# HeadAmp.net
KiCad netlist of a schematic drawn in EAGLE
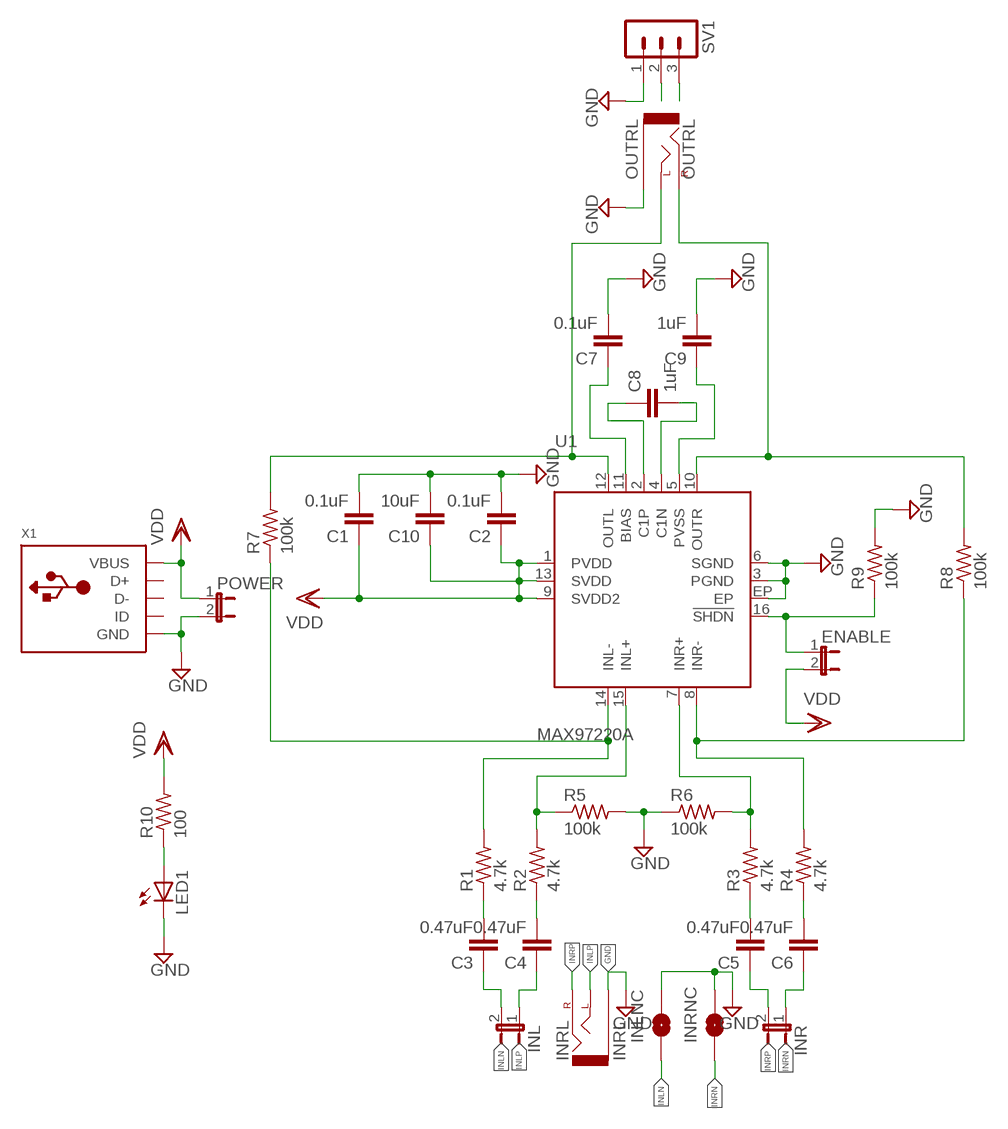
[diagram p0: schematic, sheet 1]

(export (version "E")
  (design (tool "Eeschema 10.0.6"))
  (components
    (comp (ref "C1")
      (value "0.1uF")
      (footprint "eagle-import:C0603")
      (libsource (lib "eagle-import") (part "C-EUC0603"))
    )
    (comp (ref "C2")
      (value "0.1uF")
      (footprint "eagle-import:C0603")
      (libsource (lib "eagle-import") (part "C-EUC0603"))
    )
    (comp (ref "C3")
      (value "0.47uF")
      (footprint "eagle-import:C0603")
      (libsource (lib "eagle-import") (part "C-EUC0603"))
    )
    (comp (ref "C4")
      (value "0.47uF")
      (footprint "eagle-import:C0603")
      (libsource (lib "eagle-import") (part "C-EUC0603"))
    )
    (comp (ref "C5")
      (value "0.47uF")
      (footprint "eagle-import:C0603")
      (libsource (lib "eagle-import") (part "C-EUC0603"))
    )
    (comp (ref "C6")
      (value "0.47uF")
      (footprint "eagle-import:C0603")
      (libsource (lib "eagle-import") (part "C-EUC0603"))
    )
    (comp (ref "C7")
      (value "0.1uF")
      (footprint "eagle-import:C0603")
      (libsource (lib "eagle-import") (part "C-EUC0603"))
    )
    (comp (ref "C8")
      (value "1uF")
      (footprint "eagle-import:C0603")
      (libsource (lib "eagle-import") (part "C-EUC0603"))
    )
    (comp (ref "C9")
      (value "1uF")
      (footprint "eagle-import:C0603")
      (libsource (lib "eagle-import") (part "C-EUC0603"))
    )
    (comp (ref "C10")
      (value "10uF")
      (footprint "eagle-import:C0603")
      (libsource (lib "eagle-import") (part "C-EUC0603"))
    )
    (comp (ref "ENABLE")
      (value "JP1E")
      (footprint "eagle-import:JP1")
      (libsource (lib "eagle-import") (part "JP1E"))
    )
    (comp (ref "INL")
      (value "JP1E")
      (footprint "eagle-import:JP1")
      (libsource (lib "eagle-import") (part "JP1E"))
    )
    (comp (ref "INLNC")
      (value "SOLDERJUMPERNO")
      (footprint "eagle-import:SJ_2S-NO")
      (libsource (lib "eagle-import") (part "SOLDERJUMPERNO"))
    )
    (comp (ref "INR")
      (value "JP1E")
      (footprint "eagle-import:JP1")
      (libsource (lib "eagle-import") (part "JP1E"))
    )
    (comp (ref "INRL")
      (value "INRL")
      (footprint "eagle-import:AUDIO-JACK-3.5MM-SMD")
      (libsource (lib "eagle-import") (part "AUDIO-JACKSMD2"))
    )
    (comp (ref "INRNC")
      (value "SOLDERJUMPERNO")
      (footprint "eagle-import:SJ_2S-NO")
      (libsource (lib "eagle-import") (part "SOLDERJUMPERNO"))
    )
    (comp (ref "LED1")
      (value "LEDCHIP-LED0805")
      (footprint "eagle-import:CHIP-LED0805")
      (libsource (lib "eagle-import") (part "LEDCHIP-LED0805"))
    )
    (comp (ref "OUTRL")
      (value "OUTRL")
      (footprint "eagle-import:AUDIO-JACK-3.5MM-SMD")
      (libsource (lib "eagle-import") (part "AUDIO-JACKSMD2"))
    )
    (comp (ref "POWER")
      (value "JP1E")
      (footprint "eagle-import:JP1")
      (libsource (lib "eagle-import") (part "JP1E"))
    )
    (comp (ref "R1")
      (value "4.7k")
      (footprint "eagle-import:R0603")
      (libsource (lib "eagle-import") (part "R-US_R0603"))
    )
    (comp (ref "R2")
      (value "4.7k")
      (footprint "eagle-import:R0603")
      (libsource (lib "eagle-import") (part "R-US_R0603"))
    )
    (comp (ref "R3")
      (value "4.7k")
      (footprint "eagle-import:R0603")
      (libsource (lib "eagle-import") (part "R-US_R0603"))
    )
    (comp (ref "R4")
      (value "4.7k")
      (footprint "eagle-import:R0603")
      (libsource (lib "eagle-import") (part "R-US_R0603"))
    )
    (comp (ref "R5")
      (value "100k")
      (footprint "eagle-import:R0603")
      (libsource (lib "eagle-import") (part "R-US_R0603"))
    )
    (comp (ref "R6")
      (value "100k")
      (footprint "eagle-import:R0603")
      (libsource (lib "eagle-import") (part "R-US_R0603"))
    )
    (comp (ref "R7")
      (value "100k")
      (footprint "eagle-import:R0603")
      (libsource (lib "eagle-import") (part "R-US_R0603"))
    )
    (comp (ref "R8")
      (value "100k")
      (footprint "eagle-import:R0603")
      (libsource (lib "eagle-import") (part "R-US_R0603"))
    )
    (comp (ref "R9")
      (value "100k")
      (footprint "eagle-import:R0603")
      (libsource (lib "eagle-import") (part "R-US_R0603"))
    )
    (comp (ref "R10")
      (value "100")
      (footprint "eagle-import:R0603")
      (libsource (lib "eagle-import") (part "R-US_R0603"))
    )
    (comp (ref "SV1")
      (value "MA03-1")
      (footprint "eagle-import:MA03-1")
      (libsource (lib "eagle-import") (part "MA03-1"))
    )
    (comp (ref "U1")
      (value "MAX97220A")
      (footprint "eagle-import:TQFN16")
      (libsource (lib "eagle-import") (part "MAX97220A"))
    )
    (comp (ref "X1")
      (value "USB_MICRO_20329_V2")
      (footprint "eagle-import:4UCONN_20329_V2")
      (libsource (lib "eagle-import") (part "USB_MICRO_20329_V2"))
    )
  )
  (nets
    (net (code "1") (name "/LOUT") (class "Default")
      (node (ref "OUTRL") (pin "4") (pinfunction "4_4") (pintype "bidirectional"))
      (node (ref "R7") (pin "2") (pinfunction "2_2") (pintype "passive"))
      (node (ref "SV1") (pin "2") (pinfunction "2_2") (pintype "passive"))
      (node (ref "U1") (pin "12") (pinfunction "OUTL_12") (pintype "output"))
    )
    (net (code "2") (name "/ROUT") (class "Default")
      (node (ref "OUTRL") (pin "1") (pinfunction "1_1") (pintype "bidirectional"))
      (node (ref "R8") (pin "2") (pinfunction "2_2") (pintype "passive"))
      (node (ref "SV1") (pin "3") (pinfunction "3_3") (pintype "passive"))
      (node (ref "U1") (pin "10") (pinfunction "OUTR_10") (pintype "output"))
    )
    (net (code "3") (name "GND") (class "Default")
      (node (ref "C1") (pin "2") (pinfunction "2_2") (pintype "passive"))
      (node (ref "C10") (pin "2") (pinfunction "2_2") (pintype "passive"))
      (node (ref "C2") (pin "2") (pinfunction "2_2") (pintype "passive"))
      (node (ref "C7") (pin "2") (pinfunction "2_2") (pintype "passive"))
      (node (ref "C9") (pin "2") (pinfunction "2_2") (pintype "passive"))
      (node (ref "INLNC") (pin "2") (pinfunction "2_2") (pintype "passive"))
      (node (ref "INRL") (pin "5") (pinfunction "5_5") (pintype "bidirectional"))
      (node (ref "INRNC") (pin "2") (pinfunction "2_2") (pintype "passive"))
      (node (ref "LED1") (pin "C") (pinfunction "C_C") (pintype "passive"))
      (node (ref "OUTRL") (pin "5") (pinfunction "5_5") (pintype "bidirectional"))
      (node (ref "POWER") (pin "2") (pinfunction "2_2") (pintype "passive"))
      (node (ref "R5") (pin "2") (pinfunction "2_2") (pintype "passive"))
      (node (ref "R6") (pin "1") (pinfunction "1_1") (pintype "passive"))
      (node (ref "R9") (pin "2") (pinfunction "2_2") (pintype "passive"))
      (node (ref "SV1") (pin "1") (pinfunction "1_1") (pintype "passive"))
      (node (ref "U1") (pin "3") (pinfunction "PGND_3") (pintype "power_in"))
      (node (ref "U1") (pin "6") (pinfunction "SGND_6") (pintype "power_in"))
      (node (ref "U1") (pin "EP") (pinfunction "EP_EP") (pintype "power_in"))
      (node (ref "X1") (pin "BASE@1") (pinfunction "GND_BASE@1") (pintype "power_in"))
      (node (ref "X1") (pin "BASE@2") (pinfunction "GND_BASE@2") (pintype "power_in"))
      (node (ref "X1") (pin "GND") (pinfunction "GND_GND") (pintype "power_in"))
      (node (ref "X1") (pin "SPRT@1") (pinfunction "GND_SPRT@1") (pintype "power_in"))
      (node (ref "X1") (pin "SPRT@2") (pinfunction "GND_SPRT@2") (pintype "power_in"))
      (node (ref "X1") (pin "SPRT@3") (pinfunction "GND_SPRT@3") (pintype "power_in"))
      (node (ref "X1") (pin "SPRT@4") (pinfunction "GND_SPRT@4") (pintype "power_in"))
    )
    (net (code "4") (name "INLN") (class "Default")
      (node (ref "C3") (pin "1") (pinfunction "1_1") (pintype "passive"))
      (node (ref "INL") (pin "2") (pinfunction "2_2") (pintype "passive"))
      (node (ref "INLNC") (pin "1") (pinfunction "1_1") (pintype "passive"))
    )
    (net (code "5") (name "INLP") (class "Default")
      (node (ref "C4") (pin "1") (pinfunction "1_1") (pintype "passive"))
      (node (ref "INL") (pin "1") (pinfunction "1_1") (pintype "passive"))
      (node (ref "INRL") (pin "4") (pinfunction "4_4") (pintype "bidirectional"))
    )
    (net (code "6") (name "INRN") (class "Default")
      (node (ref "C6") (pin "1") (pinfunction "1_1") (pintype "passive"))
      (node (ref "INR") (pin "1") (pinfunction "1_1") (pintype "passive"))
      (node (ref "INRNC") (pin "1") (pinfunction "1_1") (pintype "passive"))
    )
    (net (code "7") (name "INRP") (class "Default")
      (node (ref "C5") (pin "1") (pinfunction "1_1") (pintype "passive"))
      (node (ref "INR") (pin "2") (pinfunction "2_2") (pintype "passive"))
      (node (ref "INRL") (pin "1") (pinfunction "1_1") (pintype "bidirectional"))
    )
    (net (code "8") (name "Net-(C3-Pad2)") (class "Default")
      (node (ref "C3") (pin "2") (pinfunction "2_2") (pintype "passive"))
      (node (ref "R1") (pin "1") (pinfunction "1_1") (pintype "passive"))
    )
    (net (code "9") (name "Net-(C4-Pad2)") (class "Default")
      (node (ref "C4") (pin "2") (pinfunction "2_2") (pintype "passive"))
      (node (ref "R2") (pin "1") (pinfunction "1_1") (pintype "passive"))
    )
    (net (code "10") (name "Net-(C5-Pad2)") (class "Default")
      (node (ref "C5") (pin "2") (pinfunction "2_2") (pintype "passive"))
      (node (ref "R3") (pin "1") (pinfunction "1_1") (pintype "passive"))
    )
    (net (code "11") (name "Net-(C6-Pad2)") (class "Default")
      (node (ref "C6") (pin "2") (pinfunction "2_2") (pintype "passive"))
      (node (ref "R4") (pin "1") (pinfunction "1_1") (pintype "passive"))
    )
    (net (code "12") (name "Net-(LED1-PadA)") (class "Default")
      (node (ref "LED1") (pin "A") (pinfunction "A_A") (pintype "passive"))
      (node (ref "R10") (pin "1") (pinfunction "1_1") (pintype "passive"))
    )
    (net (code "13") (name "Net-(U1-BIAS)") (class "Default")
      (node (ref "C7") (pin "1") (pinfunction "1_1") (pintype "passive"))
      (node (ref "U1") (pin "11") (pinfunction "BIAS_11") (pintype "bidirectional"))
    )
    (net (code "14") (name "Net-(U1-C1N)") (class "Default")
      (node (ref "C8") (pin "2") (pinfunction "2_2") (pintype "passive"))
      (node (ref "U1") (pin "4") (pinfunction "C1N_4") (pintype "bidirectional"))
    )
    (net (code "15") (name "Net-(U1-C1P)") (class "Default")
      (node (ref "C8") (pin "1") (pinfunction "1_1") (pintype "passive"))
      (node (ref "U1") (pin "2") (pinfunction "C1P_2") (pintype "bidirectional"))
    )
    (net (code "16") (name "Net-(U1-INL+)") (class "Default")
      (node (ref "R2") (pin "2") (pinfunction "2_2") (pintype "passive"))
      (node (ref "R5") (pin "1") (pinfunction "1_1") (pintype "passive"))
      (node (ref "U1") (pin "15") (pinfunction "INL+_15") (pintype "input"))
    )
    (net (code "17") (name "Net-(U1-INL-)") (class "Default")
      (node (ref "R1") (pin "2") (pinfunction "2_2") (pintype "passive"))
      (node (ref "R7") (pin "1") (pinfunction "1_1") (pintype "passive"))
      (node (ref "U1") (pin "14") (pinfunction "INL-_14") (pintype "input"))
    )
    (net (code "18") (name "Net-(U1-INR+)") (class "Default")
      (node (ref "R3") (pin "2") (pinfunction "2_2") (pintype "passive"))
      (node (ref "R6") (pin "2") (pinfunction "2_2") (pintype "passive"))
      (node (ref "U1") (pin "7") (pinfunction "INR+_7") (pintype "input"))
    )
    (net (code "19") (name "Net-(U1-INR-)") (class "Default")
      (node (ref "R4") (pin "2") (pinfunction "2_2") (pintype "passive"))
      (node (ref "R8") (pin "1") (pinfunction "1_1") (pintype "passive"))
      (node (ref "U1") (pin "8") (pinfunction "INR-_8") (pintype "input"))
    )
    (net (code "20") (name "Net-(U1-PVSS)") (class "Default")
      (node (ref "C9") (pin "1") (pinfunction "1_1") (pintype "passive"))
      (node (ref "U1") (pin "5") (pinfunction "PVSS_5") (pintype "bidirectional"))
    )
    (net (code "21") (name "Net-(U1-~{SHDN})") (class "Default")
      (node (ref "ENABLE") (pin "1") (pinfunction "1_1") (pintype "passive"))
      (node (ref "R9") (pin "1") (pinfunction "1_1") (pintype "passive"))
      (node (ref "U1") (pin "16") (pinfunction "~{SHDN}_16") (pintype "bidirectional"))
    )
    (net (code "22") (name "VDD") (class "Default")
      (node (ref "C1") (pin "1") (pinfunction "1_1") (pintype "passive"))
      (node (ref "C10") (pin "1") (pinfunction "1_1") (pintype "passive"))
      (node (ref "C2") (pin "1") (pinfunction "1_1") (pintype "passive"))
      (node (ref "ENABLE") (pin "2") (pinfunction "2_2") (pintype "passive"))
      (node (ref "POWER") (pin "1") (pinfunction "1_1") (pintype "passive"))
      (node (ref "R10") (pin "2") (pinfunction "2_2") (pintype "passive"))
      (node (ref "U1") (pin "1") (pinfunction "PVDD_1") (pintype "power_in"))
      (node (ref "U1") (pin "13") (pinfunction "SVDD_13") (pintype "power_in"))
      (node (ref "U1") (pin "9") (pinfunction "SVDD2_9") (pintype "power_in"))
      (node (ref "X1") (pin "VBUS") (pinfunction "VBUS_VBUS") (pintype "power_in"))
    )
    (net (code "23") (name "unconnected-(X1-PadD+)") (class "Default")
      (node (ref "X1") (pin "D+") (pinfunction "D+_D+") (pintype "bidirectional"))
    )
    (net (code "24") (name "unconnected-(X1-PadD-)") (class "Default")
      (node (ref "X1") (pin "D-") (pinfunction "D-_D-") (pintype "bidirectional"))
    )
    (net (code "25") (name "unconnected-(X1-PadID)") (class "Default")
      (node (ref "X1") (pin "ID") (pinfunction "ID_ID") (pintype "bidirectional"))
    )
  )
)
